# Main.net
KiCad netlist of a schematic drawn in Altium Designer
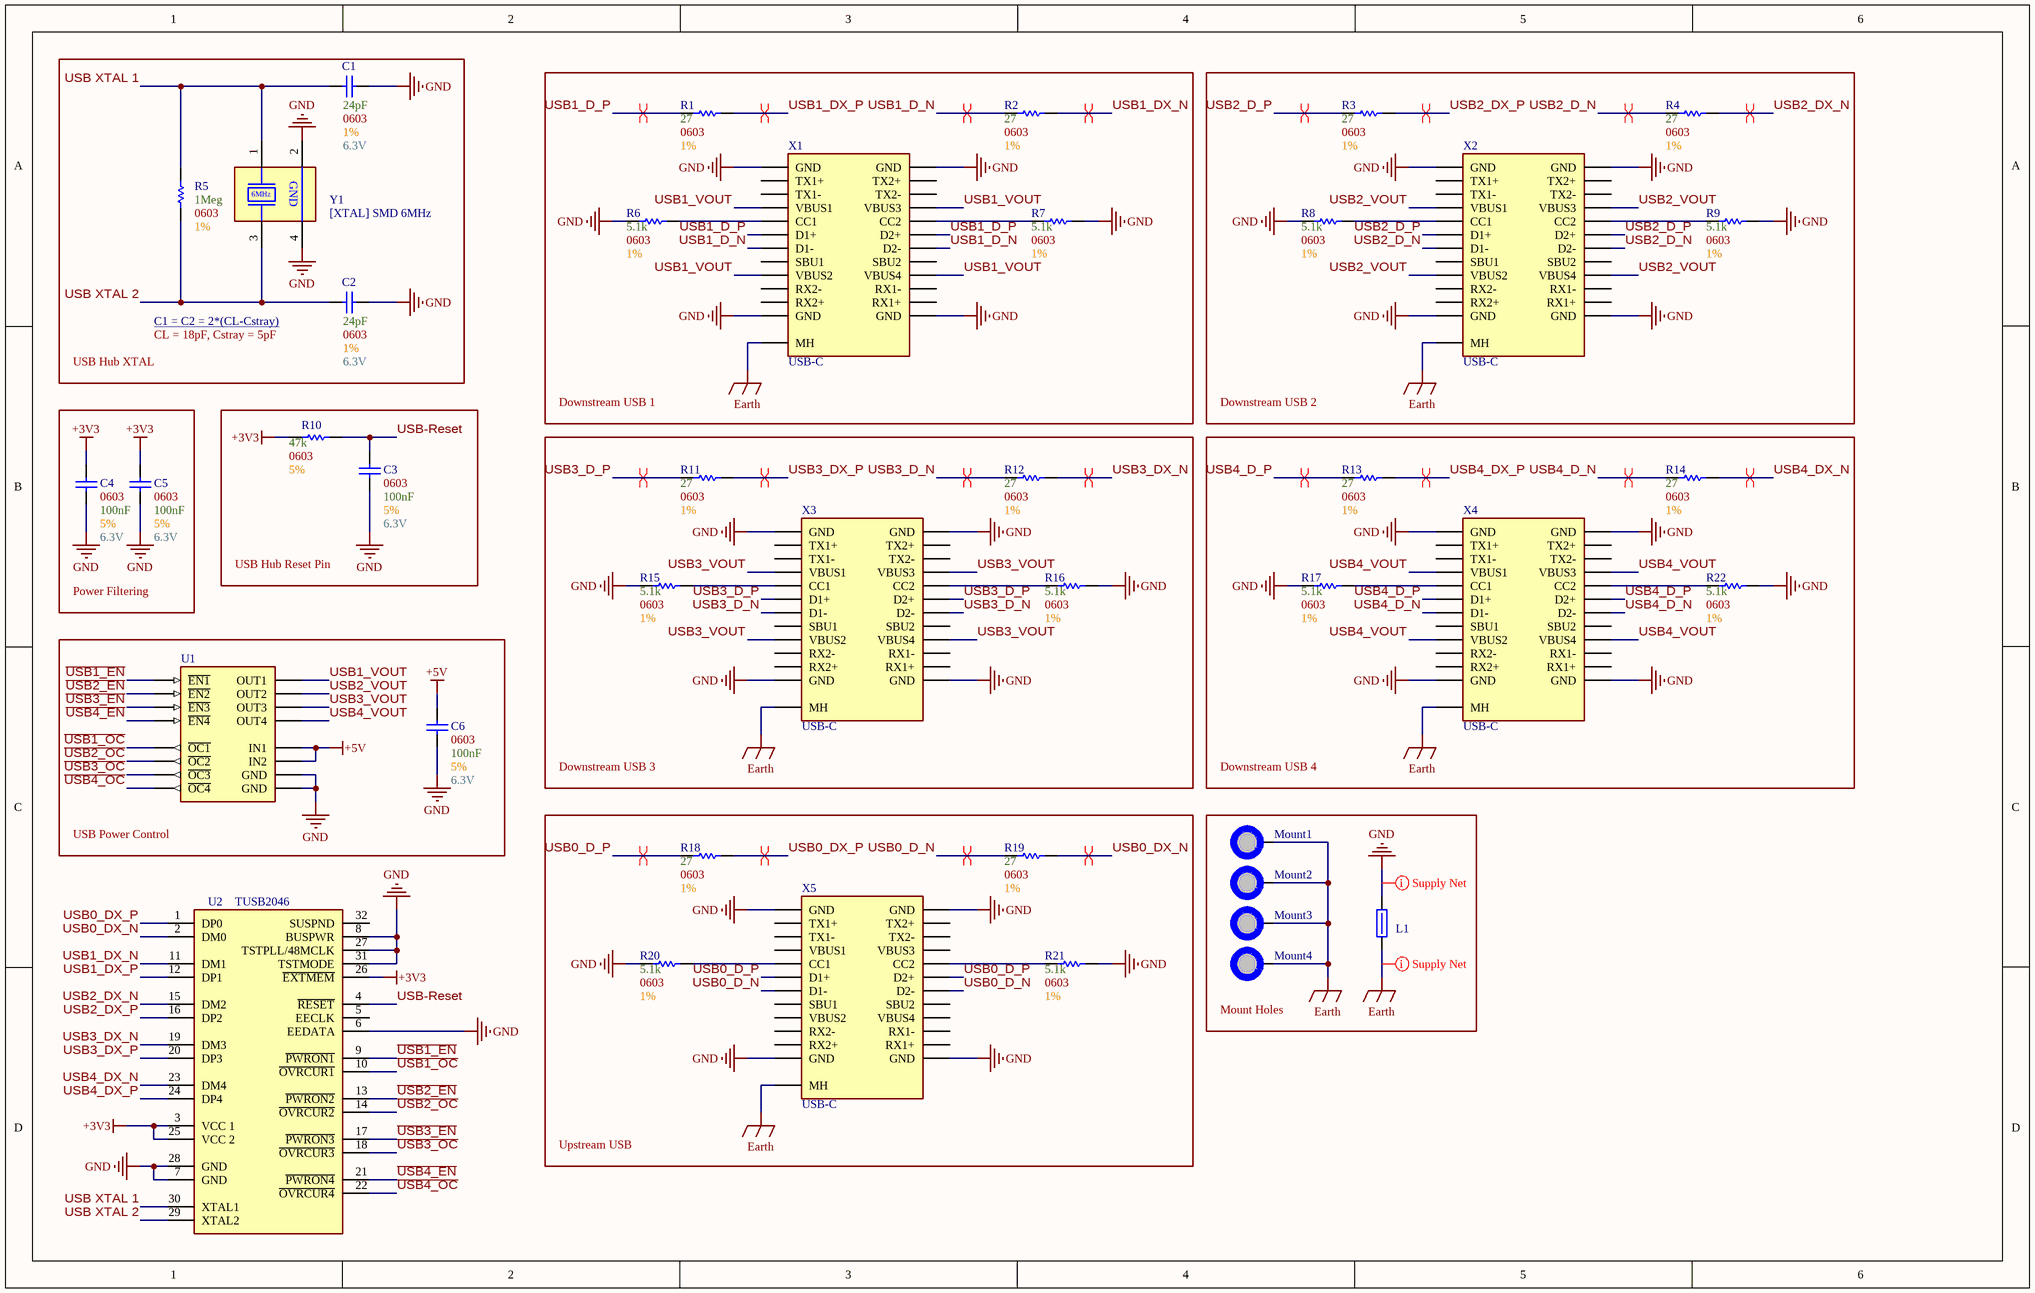
[diagram p0: Main.SchDoc]

(export (version "E")
  (design (tool "Eeschema 10.0.6"))
  (components
    (comp (ref "C1")
      (value "SMD Nonpolarized")
      (footprint "[Cap] SMD 0603")
      (fields
        (field (name "TOLERANCE") "1%")
        (field (name "SIZE PACKAGE") "0603")
        (field (name "CAPACITANCE") "24pF")
        (field (name "VOLTAGE") "6.3V")
      )
      (libsource (lib "RADM Components") (part "[Cap] SMD Nonpolarized"))
    )
    (comp (ref "C2")
      (value "SMD Nonpolarized")
      (footprint "[Cap] SMD 0603")
      (fields
        (field (name "TOLERANCE") "1%")
        (field (name "SIZE PACKAGE") "0603")
        (field (name "CAPACITANCE") "24pF")
        (field (name "VOLTAGE") "6.3V")
      )
      (libsource (lib "RADM Components") (part "[Cap] SMD Nonpolarized"))
    )
    (comp (ref "C3")
      (value "[Cap] SMD Nonpolarized")
      (footprint "[Cap] SMD 0603")
      (fields
        (field (name "SIZE PACKAGE") "0603")
        (field (name "CAPACITANCE") "100nF")
        (field (name "VOLTAGE") "6.3V")
        (field (name "TOLERANCE") "5%")
      )
      (libsource (lib "RADM Components") (part "[Cap] SMD Nonpolarized"))
    )
    (comp (ref "C4")
      (value "[Cap] SMD Nonpolarized")
      (footprint "[Cap] SMD 0603")
      (fields
        (field (name "SIZE PACKAGE") "0603")
        (field (name "CAPACITANCE") "100nF")
        (field (name "VOLTAGE") "6.3V")
        (field (name "TOLERANCE") "5%")
      )
      (libsource (lib "RADM Components") (part "[Cap] SMD Nonpolarized"))
    )
    (comp (ref "C5")
      (value "[Cap] SMD Nonpolarized")
      (footprint "[Cap] SMD 0603")
      (fields
        (field (name "SIZE PACKAGE") "0603")
        (field (name "CAPACITANCE") "100nF")
        (field (name "VOLTAGE") "6.3V")
        (field (name "TOLERANCE") "5%")
      )
      (libsource (lib "RADM Components") (part "[Cap] SMD Nonpolarized"))
    )
    (comp (ref "C6")
      (value "[Cap] SMD Nonpolarized")
      (footprint "[Cap] SMD 0603")
      (fields
        (field (name "SIZE PACKAGE") "0603")
        (field (name "CAPACITANCE") "100nF")
        (field (name "VOLTAGE") "6.3V")
        (field (name "TOLERANCE") "5%")
      )
      (libsource (lib "RADM Components") (part "[Cap] SMD Nonpolarized"))
    )
    (comp (ref "L1")
      (value "652-MH2029-300Y")
      (footprint "[Ferrite] SMD Bead 0805 (1)")
      (libsource (lib "RADM Components") (part "[Ferrite] SMD Ferrite Bead (1)"))
    )
    (comp (ref "Mount1")
      (value "M3 Mount Hole")
      (footprint "[Mount] M3 Mount Hole")
      (description "Place at least 4.5mm from board edge. Plated.")
      (libsource (lib "RADM Connectors") (part "[Mount] M3 Mount Hole"))
    )
    (comp (ref "Mount2")
      (value "M3 Mount Hole")
      (footprint "[Mount] M3 Mount Hole")
      (description "Place at least 4.5mm from board edge. Plated.")
      (libsource (lib "RADM Connectors") (part "[Mount] M3 Mount Hole"))
    )
    (comp (ref "Mount3")
      (value "M3 Mount Hole")
      (footprint "[Mount] M3 Mount Hole")
      (description "Place at least 4.5mm from board edge. Plated.")
      (libsource (lib "RADM Connectors") (part "[Mount] M3 Mount Hole"))
    )
    (comp (ref "Mount4")
      (value "M3 Mount Hole")
      (footprint "[Mount] M3 Mount Hole")
      (description "Place at least 4.5mm from board edge. Plated.")
      (libsource (lib "RADM Connectors") (part "[Mount] M3 Mount Hole"))
    )
    (comp (ref "R1")
      (value "[Res] SMD Resistor")
      (footprint "[Res] SMD 0603")
      (description "Generic")
      (fields
        (field (name "TOLERANCE") "1%")
        (field (name "RESISTANCE") "27")
        (field (name "SIZE PACKAGE") "0603")
      )
      (libsource (lib "RADM Components") (part "[Res] SMD Resistor"))
    )
    (comp (ref "R2")
      (value "[Res] SMD Resistor")
      (footprint "[Res] SMD 0603")
      (description "Generic")
      (fields
        (field (name "TOLERANCE") "1%")
        (field (name "RESISTANCE") "27")
        (field (name "SIZE PACKAGE") "0603")
      )
      (libsource (lib "RADM Components") (part "[Res] SMD Resistor"))
    )
    (comp (ref "R3")
      (value "[Res] SMD Resistor")
      (footprint "[Res] SMD 0603")
      (description "Generic")
      (fields
        (field (name "TOLERANCE") "1%")
        (field (name "RESISTANCE") "27")
        (field (name "SIZE PACKAGE") "0603")
      )
      (libsource (lib "RADM Components") (part "[Res] SMD Resistor"))
    )
    (comp (ref "R4")
      (value "[Res] SMD Resistor")
      (footprint "[Res] SMD 0603")
      (description "Generic")
      (fields
        (field (name "TOLERANCE") "1%")
        (field (name "RESISTANCE") "27")
        (field (name "SIZE PACKAGE") "0603")
      )
      (libsource (lib "RADM Components") (part "[Res] SMD Resistor"))
    )
    (comp (ref "R5")
      (value "[Res] SMD Resistor")
      (footprint "[Res] SMD 0603")
      (description "Generic")
      (fields
        (field (name "TOLERANCE") "1%")
        (field (name "RESISTANCE") "1Meg")
        (field (name "SIZE PACKAGE") "0603")
      )
      (libsource (lib "RADM Components") (part "[Res] SMD Resistor"))
    )
    (comp (ref "R6")
      (value "[Res] SMD Resistor")
      (footprint "[Res] SMD 0603")
      (description "Generic")
      (fields
        (field (name "TOLERANCE") "1%")
        (field (name "RESISTANCE") "5.1k")
        (field (name "SIZE PACKAGE") "0603")
      )
      (libsource (lib "RADM Components") (part "[Res] SMD Resistor"))
    )
    (comp (ref "R7")
      (value "[Res] SMD Resistor")
      (footprint "[Res] SMD 0603")
      (description "Generic")
      (fields
        (field (name "TOLERANCE") "1%")
        (field (name "RESISTANCE") "5.1k")
        (field (name "SIZE PACKAGE") "0603")
      )
      (libsource (lib "RADM Components") (part "[Res] SMD Resistor"))
    )
    (comp (ref "R8")
      (value "[Res] SMD Resistor")
      (footprint "[Res] SMD 0603")
      (description "Generic")
      (fields
        (field (name "TOLERANCE") "1%")
        (field (name "RESISTANCE") "5.1k")
        (field (name "SIZE PACKAGE") "0603")
      )
      (libsource (lib "RADM Components") (part "[Res] SMD Resistor"))
    )
    (comp (ref "R9")
      (value "[Res] SMD Resistor")
      (footprint "[Res] SMD 0603")
      (description "Generic")
      (fields
        (field (name "TOLERANCE") "1%")
        (field (name "RESISTANCE") "5.1k")
        (field (name "SIZE PACKAGE") "0603")
      )
      (libsource (lib "RADM Components") (part "[Res] SMD Resistor"))
    )
    (comp (ref "R10")
      (value "[Res] SMD Resistor")
      (footprint "[Res] SMD 0603")
      (description "Generic")
      (fields
        (field (name "TOLERANCE") "5%")
        (field (name "RESISTANCE") "47k")
        (field (name "SIZE PACKAGE") "0603")
      )
      (libsource (lib "RADM Components") (part "[Res] SMD Resistor"))
    )
    (comp (ref "R11")
      (value "[Res] SMD Resistor")
      (footprint "[Res] SMD 0603")
      (description "Generic")
      (fields
        (field (name "TOLERANCE") "1%")
        (field (name "RESISTANCE") "27")
        (field (name "SIZE PACKAGE") "0603")
      )
      (libsource (lib "RADM Components") (part "[Res] SMD Resistor"))
    )
    (comp (ref "R12")
      (value "[Res] SMD Resistor")
      (footprint "[Res] SMD 0603")
      (description "Generic")
      (fields
        (field (name "TOLERANCE") "1%")
        (field (name "RESISTANCE") "27")
        (field (name "SIZE PACKAGE") "0603")
      )
      (libsource (lib "RADM Components") (part "[Res] SMD Resistor"))
    )
    (comp (ref "R13")
      (value "[Res] SMD Resistor")
      (footprint "[Res] SMD 0603")
      (description "Generic")
      (fields
        (field (name "TOLERANCE") "1%")
        (field (name "RESISTANCE") "27")
        (field (name "SIZE PACKAGE") "0603")
      )
      (libsource (lib "RADM Components") (part "[Res] SMD Resistor"))
    )
    (comp (ref "R14")
      (value "[Res] SMD Resistor")
      (footprint "[Res] SMD 0603")
      (description "Generic")
      (fields
        (field (name "TOLERANCE") "1%")
        (field (name "RESISTANCE") "27")
        (field (name "SIZE PACKAGE") "0603")
      )
      (libsource (lib "RADM Components") (part "[Res] SMD Resistor"))
    )
    (comp (ref "R15")
      (value "[Res] SMD Resistor")
      (footprint "[Res] SMD 0603")
      (description "Generic")
      (fields
        (field (name "TOLERANCE") "1%")
        (field (name "RESISTANCE") "5.1k")
        (field (name "SIZE PACKAGE") "0603")
      )
      (libsource (lib "RADM Components") (part "[Res] SMD Resistor"))
    )
    (comp (ref "R16")
      (value "[Res] SMD Resistor")
      (footprint "[Res] SMD 0603")
      (description "Generic")
      (fields
        (field (name "TOLERANCE") "1%")
        (field (name "RESISTANCE") "5.1k")
        (field (name "SIZE PACKAGE") "0603")
      )
      (libsource (lib "RADM Components") (part "[Res] SMD Resistor"))
    )
    (comp (ref "R17")
      (value "[Res] SMD Resistor")
      (footprint "[Res] SMD 0603")
      (description "Generic")
      (fields
        (field (name "TOLERANCE") "1%")
        (field (name "RESISTANCE") "5.1k")
        (field (name "SIZE PACKAGE") "0603")
      )
      (libsource (lib "RADM Components") (part "[Res] SMD Resistor"))
    )
    (comp (ref "R18")
      (value "[Res] SMD Resistor")
      (footprint "[Res] SMD 0603")
      (description "Generic")
      (fields
        (field (name "TOLERANCE") "1%")
        (field (name "RESISTANCE") "27")
        (field (name "SIZE PACKAGE") "0603")
      )
      (libsource (lib "RADM Components") (part "[Res] SMD Resistor"))
    )
    (comp (ref "R19")
      (value "[Res] SMD Resistor")
      (footprint "[Res] SMD 0603")
      (description "Generic")
      (fields
        (field (name "TOLERANCE") "1%")
        (field (name "RESISTANCE") "27")
        (field (name "SIZE PACKAGE") "0603")
      )
      (libsource (lib "RADM Components") (part "[Res] SMD Resistor"))
    )
    (comp (ref "R20")
      (value "[Res] SMD Resistor")
      (footprint "[Res] SMD 0603")
      (description "Generic")
      (fields
        (field (name "TOLERANCE") "1%")
        (field (name "RESISTANCE") "5.1k")
        (field (name "SIZE PACKAGE") "0603")
      )
      (libsource (lib "RADM Components") (part "[Res] SMD Resistor"))
    )
    (comp (ref "R21")
      (value "[Res] SMD Resistor")
      (footprint "[Res] SMD 0603")
      (description "Generic")
      (fields
        (field (name "TOLERANCE") "1%")
        (field (name "RESISTANCE") "5.1k")
        (field (name "SIZE PACKAGE") "0603")
      )
      (libsource (lib "RADM Components") (part "[Res] SMD Resistor"))
    )
    (comp (ref "R22")
      (value "[Res] SMD Resistor")
      (footprint "[Res] SMD 0603")
      (description "Generic")
      (fields
        (field (name "TOLERANCE") "1%")
        (field (name "RESISTANCE") "5.1k")
        (field (name "SIZE PACKAGE") "0603")
      )
      (libsource (lib "RADM Components") (part "[Res] SMD Resistor"))
    )
    (comp (ref "U1")
      (value "[IC] USB Hub Power Distribution")
      (footprint "[IC] USB Hub Power Distribution")
      (libsource (lib "RADM Components") (part "[IC] USB Hub Power Distribution"))
    )
    (comp (ref "U2")
      (value "TUSB2046")
      (footprint "[IC] USB Hub 4port (2)")
      (description "TUSB2046BVFR")
      (libsource (lib "RADM Components") (part "[IC] USB Hub 4port (2)"))
    )
    (comp (ref "X1")
      (value "USB-C")
      (footprint "[Port] USB-C")
      (libsource (lib "RADM Connectors") (part "[Port] USB Type-C"))
    )
    (comp (ref "X2")
      (value "USB-C")
      (footprint "[Port] USB-C")
      (libsource (lib "RADM Connectors") (part "[Port] USB Type-C"))
    )
    (comp (ref "X3")
      (value "USB-C")
      (footprint "[Port] USB-C")
      (libsource (lib "RADM Connectors") (part "[Port] USB Type-C"))
    )
    (comp (ref "X4")
      (value "USB-C")
      (footprint "[Port] USB-C")
      (libsource (lib "RADM Connectors") (part "[Port] USB Type-C"))
    )
    (comp (ref "X5")
      (value "USB-C")
      (footprint "[Port] USB-C")
      (libsource (lib "RADM Connectors") (part "[Port] USB Type-C"))
    )
    (comp (ref "Y1")
      (value "[XTAL] SMD 6MHz")
      (footprint "[XTAL] SMD 6MHz")
      (description "ECS-060-18-20BM-JEN-TR")
      (libsource (lib "RADM Components") (part "[XTAL] SMD 6MHz"))
    )
  )
  (nets
    (net (code "1") (name "+3V3") (class "Default")
      (node (ref "C4") (pin "2") (pinfunction "2_2") (pintype "passive"))
      (node (ref "C5") (pin "2") (pinfunction "2_2") (pintype "passive"))
      (node (ref "R10") (pin "1") (pinfunction "1_1") (pintype "passive"))
      (node (ref "U2") (pin "25") (pinfunction "VCC_2_25") (pintype "passive"))
      (node (ref "U2") (pin "26") (pinfunction "~{EXTMEM}_26") (pintype "passive"))
      (node (ref "U2") (pin "3") (pinfunction "VCC_1_3") (pintype "passive"))
    )
    (net (code "2") (name "+5V") (class "Default")
      (node (ref "C6") (pin "2") (pinfunction "2_2") (pintype "passive"))
      (node (ref "U1") (pin "2") (pinfunction "IN1_2") (pintype "power_in"))
      (node (ref "U1") (pin "6") (pinfunction "IN2_6") (pintype "power_in"))
    )
    (net (code "3") (name "/USB XTAL 1") (class "Default")
      (node (ref "C1") (pin "1") (pinfunction "1_1") (pintype "passive"))
      (node (ref "R5") (pin "1") (pinfunction "1_1") (pintype "passive"))
      (node (ref "U2") (pin "30") (pinfunction "XTAL1_30") (pintype "passive"))
      (node (ref "Y1") (pin "1") (pinfunction "XTAL1_1") (pintype "power_in"))
    )
    (net (code "4") (name "/USB XTAL 2") (class "Default")
      (node (ref "C2") (pin "1") (pinfunction "1_1") (pintype "passive"))
      (node (ref "R5") (pin "2") (pinfunction "2_2") (pintype "passive"))
      (node (ref "U2") (pin "29") (pinfunction "XTAL2_29") (pintype "passive"))
      (node (ref "Y1") (pin "3") (pinfunction "XTAL2_3") (pintype "power_in"))
    )
    (net (code "5") (name "/USB-Reset") (class "Default")
      (node (ref "C3") (pin "2") (pinfunction "2_2") (pintype "passive"))
      (node (ref "R10") (pin "2") (pinfunction "2_2") (pintype "passive"))
      (node (ref "U2") (pin "4") (pinfunction "~{RESET}_4") (pintype "passive"))
    )
    (net (code "6") (name "/USB0_DX_N") (class "Default")
      (node (ref "R19") (pin "2") (pinfunction "2_2") (pintype "passive"))
      (node (ref "U2") (pin "2") (pinfunction "DM0_2") (pintype "passive"))
    )
    (net (code "7") (name "/USB0_DX_P") (class "Default")
      (node (ref "R18") (pin "2") (pinfunction "2_2") (pintype "passive"))
      (node (ref "U2") (pin "1") (pinfunction "DP0_1") (pintype "passive"))
    )
    (net (code "8") (name "/USB0_D_N") (class "Default")
      (node (ref "R19") (pin "1") (pinfunction "1_1") (pintype "passive"))
      (node (ref "X5") (pin "A7") (pinfunction "D1-_A7") (pintype "passive"))
      (node (ref "X5") (pin "B7") (pinfunction "D2-_B7") (pintype "passive"))
    )
    (net (code "9") (name "/USB0_D_P") (class "Default")
      (node (ref "R18") (pin "1") (pinfunction "1_1") (pintype "passive"))
      (node (ref "X5") (pin "A6") (pinfunction "D1+_A6") (pintype "passive"))
      (node (ref "X5") (pin "B6") (pinfunction "D2+_B6") (pintype "passive"))
    )
    (net (code "10") (name "/USB1_DX_N") (class "Default")
      (node (ref "R2") (pin "2") (pinfunction "2_2") (pintype "passive"))
      (node (ref "U2") (pin "11") (pinfunction "DM1_11") (pintype "passive"))
    )
    (net (code "11") (name "/USB1_DX_P") (class "Default")
      (node (ref "R1") (pin "2") (pinfunction "2_2") (pintype "passive"))
      (node (ref "U2") (pin "12") (pinfunction "DP1_12") (pintype "passive"))
    )
    (net (code "12") (name "/USB1_D_N") (class "Default")
      (node (ref "R2") (pin "1") (pinfunction "1_1") (pintype "passive"))
      (node (ref "X1") (pin "A7") (pinfunction "D1-_A7") (pintype "passive"))
      (node (ref "X1") (pin "B7") (pinfunction "D2-_B7") (pintype "passive"))
    )
    (net (code "13") (name "/USB1_D_P") (class "Default")
      (node (ref "R1") (pin "1") (pinfunction "1_1") (pintype "passive"))
      (node (ref "X1") (pin "A6") (pinfunction "D1+_A6") (pintype "passive"))
      (node (ref "X1") (pin "B6") (pinfunction "D2+_B6") (pintype "passive"))
    )
    (net (code "14") (name "/USB1_EN") (class "Default")
      (node (ref "U1") (pin "3") (pinfunction "~{EN1}_3") (pintype "input"))
      (node (ref "U2") (pin "9") (pinfunction "~{PWRON1}_9") (pintype "passive"))
    )
    (net (code "15") (name "/USB1_OC") (class "Default")
      (node (ref "U1") (pin "16") (pinfunction "~{OC1}_16") (pintype "output"))
      (node (ref "U2") (pin "10") (pinfunction "~{OVRCUR1}_10") (pintype "passive"))
    )
    (net (code "16") (name "/USB1_VOUT") (class "Default")
      (node (ref "U1") (pin "15") (pinfunction "OUT1_15") (pintype "power_in"))
      (node (ref "X1") (pin "A4") (pinfunction "VBUS1_A4") (pintype "passive"))
      (node (ref "X1") (pin "A9") (pinfunction "VBUS2_A9") (pintype "passive"))
      (node (ref "X1") (pin "B4") (pinfunction "VBUS3_B4") (pintype "passive"))
      (node (ref "X1") (pin "B9") (pinfunction "VBUS4_B9") (pintype "passive"))
    )
    (net (code "17") (name "/USB2_DX_N") (class "Default")
      (node (ref "R4") (pin "2") (pinfunction "2_2") (pintype "passive"))
      (node (ref "U2") (pin "15") (pinfunction "DM2_15") (pintype "passive"))
    )
    (net (code "18") (name "/USB2_DX_P") (class "Default")
      (node (ref "R3") (pin "2") (pinfunction "2_2") (pintype "passive"))
      (node (ref "U2") (pin "16") (pinfunction "DP2_16") (pintype "passive"))
    )
    (net (code "19") (name "/USB2_D_N") (class "Default")
      (node (ref "R4") (pin "1") (pinfunction "1_1") (pintype "passive"))
      (node (ref "X2") (pin "A7") (pinfunction "D1-_A7") (pintype "passive"))
      (node (ref "X2") (pin "B7") (pinfunction "D2-_B7") (pintype "passive"))
    )
    (net (code "20") (name "/USB2_D_P") (class "Default")
      (node (ref "R3") (pin "1") (pinfunction "1_1") (pintype "passive"))
      (node (ref "X2") (pin "A6") (pinfunction "D1+_A6") (pintype "passive"))
      (node (ref "X2") (pin "B6") (pinfunction "D2+_B6") (pintype "passive"))
    )
    (net (code "21") (name "/USB2_EN") (class "Default")
      (node (ref "U1") (pin "4") (pinfunction "~{EN2}_4") (pintype "input"))
      (node (ref "U2") (pin "13") (pinfunction "~{PWRON2}_13") (pintype "passive"))
    )
    (net (code "22") (name "/USB2_OC") (class "Default")
      (node (ref "U1") (pin "13") (pinfunction "~{OC2}_13") (pintype "output"))
      (node (ref "U2") (pin "14") (pinfunction "~{OVRCUR2}_14") (pintype "passive"))
    )
    (net (code "23") (name "/USB2_VOUT") (class "Default")
      (node (ref "U1") (pin "14") (pinfunction "OUT2_14") (pintype "power_in"))
      (node (ref "X2") (pin "A4") (pinfunction "VBUS1_A4") (pintype "passive"))
      (node (ref "X2") (pin "A9") (pinfunction "VBUS2_A9") (pintype "passive"))
      (node (ref "X2") (pin "B4") (pinfunction "VBUS3_B4") (pintype "passive"))
      (node (ref "X2") (pin "B9") (pinfunction "VBUS4_B9") (pintype "passive"))
    )
    (net (code "24") (name "/USB3_DX_N") (class "Default")
      (node (ref "R12") (pin "2") (pinfunction "2_2") (pintype "passive"))
      (node (ref "U2") (pin "19") (pinfunction "DM3_19") (pintype "passive"))
    )
    (net (code "25") (name "/USB3_DX_P") (class "Default")
      (node (ref "R11") (pin "2") (pinfunction "2_2") (pintype "passive"))
      (node (ref "U2") (pin "20") (pinfunction "DP3_20") (pintype "passive"))
    )
    (net (code "26") (name "/USB3_D_N") (class "Default")
      (node (ref "R12") (pin "1") (pinfunction "1_1") (pintype "passive"))
      (node (ref "X3") (pin "A7") (pinfunction "D1-_A7") (pintype "passive"))
      (node (ref "X3") (pin "B7") (pinfunction "D2-_B7") (pintype "passive"))
    )
    (net (code "27") (name "/USB3_D_P") (class "Default")
      (node (ref "R11") (pin "1") (pinfunction "1_1") (pintype "passive"))
      (node (ref "X3") (pin "A6") (pinfunction "D1+_A6") (pintype "passive"))
      (node (ref "X3") (pin "B6") (pinfunction "D2+_B6") (pintype "passive"))
    )
    (net (code "28") (name "/USB3_EN") (class "Default")
      (node (ref "U1") (pin "7") (pinfunction "~{EN3}_7") (pintype "input"))
      (node (ref "U2") (pin "17") (pinfunction "~{PWRON3}_17") (pintype "passive"))
    )
    (net (code "29") (name "/USB3_OC") (class "Default")
      (node (ref "U1") (pin "12") (pinfunction "~{OC3}_12") (pintype "output"))
      (node (ref "U2") (pin "18") (pinfunction "~{OVRCUR3}_18") (pintype "passive"))
    )
    (net (code "30") (name "/USB3_VOUT") (class "Default")
      (node (ref "U1") (pin "11") (pinfunction "OUT3_11") (pintype "power_in"))
      (node (ref "X3") (pin "A4") (pinfunction "VBUS1_A4") (pintype "passive"))
      (node (ref "X3") (pin "A9") (pinfunction "VBUS2_A9") (pintype "passive"))
      (node (ref "X3") (pin "B4") (pinfunction "VBUS3_B4") (pintype "passive"))
      (node (ref "X3") (pin "B9") (pinfunction "VBUS4_B9") (pintype "passive"))
    )
    (net (code "31") (name "/USB4_DX_N") (class "Default")
      (node (ref "R14") (pin "2") (pinfunction "2_2") (pintype "passive"))
      (node (ref "U2") (pin "23") (pinfunction "DM4_23") (pintype "passive"))
    )
    (net (code "32") (name "/USB4_DX_P") (class "Default")
      (node (ref "R13") (pin "2") (pinfunction "2_2") (pintype "passive"))
      (node (ref "U2") (pin "24") (pinfunction "DP4_24") (pintype "passive"))
    )
    (net (code "33") (name "/USB4_D_N") (class "Default")
      (node (ref "R14") (pin "1") (pinfunction "1_1") (pintype "passive"))
      (node (ref "X4") (pin "A7") (pinfunction "D1-_A7") (pintype "passive"))
      (node (ref "X4") (pin "B7") (pinfunction "D2-_B7") (pintype "passive"))
    )
    (net (code "34") (name "/USB4_D_P") (class "Default")
      (node (ref "R13") (pin "1") (pinfunction "1_1") (pintype "passive"))
      (node (ref "X4") (pin "A6") (pinfunction "D1+_A6") (pintype "passive"))
      (node (ref "X4") (pin "B6") (pinfunction "D2+_B6") (pintype "passive"))
    )
    (net (code "35") (name "/USB4_EN") (class "Default")
      (node (ref "U1") (pin "8") (pinfunction "~{EN4}_8") (pintype "input"))
      (node (ref "U2") (pin "21") (pinfunction "~{PWRON4}_21") (pintype "passive"))
    )
    (net (code "36") (name "/USB4_OC") (class "Default")
      (node (ref "U1") (pin "9") (pinfunction "~{OC4}_9") (pintype "output"))
      (node (ref "U2") (pin "22") (pinfunction "~{OVRCUR4}_22") (pintype "passive"))
    )
    (net (code "37") (name "/USB4_VOUT") (class "Default")
      (node (ref "U1") (pin "10") (pinfunction "OUT4_10") (pintype "power_in"))
      (node (ref "X4") (pin "A4") (pinfunction "VBUS1_A4") (pintype "passive"))
      (node (ref "X4") (pin "A9") (pinfunction "VBUS2_A9") (pintype "passive"))
      (node (ref "X4") (pin "B4") (pinfunction "VBUS3_B4") (pintype "passive"))
      (node (ref "X4") (pin "B9") (pinfunction "VBUS4_B9") (pintype "passive"))
    )
    (net (code "38") (name "Earth") (class "Default")
      (node (ref "L1") (pin "1") (pinfunction "1_1") (pintype "passive"))
      (node (ref "Mount1") (pin "1") (pintype "power_in"))
      (node (ref "Mount2") (pin "1") (pintype "power_in"))
      (node (ref "Mount3") (pin "1") (pintype "power_in"))
      (node (ref "Mount4") (pin "1") (pintype "power_in"))
      (node (ref "X1") (pin "MH") (pinfunction "MH_MH") (pintype "passive"))
      (node (ref "X2") (pin "MH") (pinfunction "MH_MH") (pintype "passive"))
      (node (ref "X3") (pin "MH") (pinfunction "MH_MH") (pintype "passive"))
      (node (ref "X4") (pin "MH") (pinfunction "MH_MH") (pintype "passive"))
      (node (ref "X5") (pin "MH") (pinfunction "MH_MH") (pintype "passive"))
    )
    (net (code "39") (name "GND") (class "Default")
      (node (ref "C1") (pin "2") (pinfunction "2_2") (pintype "passive"))
      (node (ref "C2") (pin "2") (pinfunction "2_2") (pintype "passive"))
      (node (ref "C3") (pin "1") (pinfunction "1_1") (pintype "passive"))
      (node (ref "C4") (pin "1") (pinfunction "1_1") (pintype "passive"))
      (node (ref "C5") (pin "1") (pinfunction "1_1") (pintype "passive"))
      (node (ref "C6") (pin "1") (pinfunction "1_1") (pintype "passive"))
      (node (ref "L1") (pin "2") (pinfunction "2_2") (pintype "passive"))
      (node (ref "R15") (pin "1") (pinfunction "1_1") (pintype "passive"))
      (node (ref "R16") (pin "2") (pinfunction "2_2") (pintype "passive"))
      (node (ref "R17") (pin "1") (pinfunction "1_1") (pintype "passive"))
      (node (ref "R20") (pin "1") (pinfunction "1_1") (pintype "passive"))
      (node (ref "R21") (pin "2") (pinfunction "2_2") (pintype "passive"))
      (node (ref "R22") (pin "2") (pinfunction "2_2") (pintype "passive"))
      (node (ref "R6") (pin "1") (pinfunction "1_1") (pintype "passive"))
      (node (ref "R7") (pin "2") (pinfunction "2_2") (pintype "passive"))
      (node (ref "R8") (pin "1") (pinfunction "1_1") (pintype "passive"))
      (node (ref "R9") (pin "2") (pinfunction "2_2") (pintype "passive"))
      (node (ref "U1") (pin "1") (pinfunction "GND_1") (pintype "power_in"))
      (node (ref "U1") (pin "5") (pinfunction "GND_5") (pintype "power_in"))
      (node (ref "U2") (pin "27") (pinfunction "TSTPLL/48MCLK_27") (pintype "passive"))
      (node (ref "U2") (pin "28") (pinfunction "GND_28") (pintype "passive"))
      (node (ref "U2") (pin "31") (pinfunction "TSTMODE_31") (pintype "passive"))
      (node (ref "U2") (pin "6") (pinfunction "EEDATA_6") (pintype "passive"))
      (node (ref "U2") (pin "7") (pinfunction "GND_7") (pintype "passive"))
      (node (ref "U2") (pin "8") (pinfunction "BUSPWR_8") (pintype "passive"))
      (node (ref "X1") (pin "A1") (pinfunction "GND_A1") (pintype "passive"))
      (node (ref "X1") (pin "A12") (pinfunction "GND_A12") (pintype "passive"))
      (node (ref "X1") (pin "B1") (pinfunction "GND_B1") (pintype "passive"))
      (node (ref "X1") (pin "B12") (pinfunction "GND_B12") (pintype "passive"))
      (node (ref "X2") (pin "A1") (pinfunction "GND_A1") (pintype "passive"))
      (node (ref "X2") (pin "A12") (pinfunction "GND_A12") (pintype "passive"))
      (node (ref "X2") (pin "B1") (pinfunction "GND_B1") (pintype "passive"))
      (node (ref "X2") (pin "B12") (pinfunction "GND_B12") (pintype "passive"))
      (node (ref "X3") (pin "A1") (pinfunction "GND_A1") (pintype "passive"))
      (node (ref "X3") (pin "A12") (pinfunction "GND_A12") (pintype "passive"))
      (node (ref "X3") (pin "B1") (pinfunction "GND_B1") (pintype "passive"))
      (node (ref "X3") (pin "B12") (pinfunction "GND_B12") (pintype "passive"))
      (node (ref "X4") (pin "A1") (pinfunction "GND_A1") (pintype "passive"))
      (node (ref "X4") (pin "A12") (pinfunction "GND_A12") (pintype "passive"))
      (node (ref "X4") (pin "B1") (pinfunction "GND_B1") (pintype "passive"))
      (node (ref "X4") (pin "B12") (pinfunction "GND_B12") (pintype "passive"))
      (node (ref "X5") (pin "A1") (pinfunction "GND_A1") (pintype "passive"))
      (node (ref "X5") (pin "A12") (pinfunction "GND_A12") (pintype "passive"))
      (node (ref "X5") (pin "B1") (pinfunction "GND_B1") (pintype "passive"))
      (node (ref "X5") (pin "B12") (pinfunction "GND_B12") (pintype "passive"))
      (node (ref "Y1") (pin "2") (pinfunction "GND_2") (pintype "power_in"))
      (node (ref "Y1") (pin "4") (pinfunction "GND_4") (pintype "power_in"))
    )
    (net (code "40") (name "Net-(X1-CC1)") (class "Default")
      (node (ref "R6") (pin "2") (pinfunction "2_2") (pintype "passive"))
      (node (ref "X1") (pin "A5") (pinfunction "CC1_A5") (pintype "passive"))
    )
    (net (code "41") (name "Net-(X1-CC2)") (class "Default")
      (node (ref "R7") (pin "1") (pinfunction "1_1") (pintype "passive"))
      (node (ref "X1") (pin "B5") (pinfunction "CC2_B5") (pintype "passive"))
    )
    (net (code "42") (name "Net-(X2-CC1)") (class "Default")
      (node (ref "R8") (pin "2") (pinfunction "2_2") (pintype "passive"))
      (node (ref "X2") (pin "A5") (pinfunction "CC1_A5") (pintype "passive"))
    )
    (net (code "43") (name "Net-(X2-CC2)") (class "Default")
      (node (ref "R9") (pin "1") (pinfunction "1_1") (pintype "passive"))
      (node (ref "X2") (pin "B5") (pinfunction "CC2_B5") (pintype "passive"))
    )
    (net (code "44") (name "Net-(X3-CC1)") (class "Default")
      (node (ref "R15") (pin "2") (pinfunction "2_2") (pintype "passive"))
      (node (ref "X3") (pin "A5") (pinfunction "CC1_A5") (pintype "passive"))
    )
    (net (code "45") (name "Net-(X3-CC2)") (class "Default")
      (node (ref "R16") (pin "1") (pinfunction "1_1") (pintype "passive"))
      (node (ref "X3") (pin "B5") (pinfunction "CC2_B5") (pintype "passive"))
    )
    (net (code "46") (name "Net-(X4-CC1)") (class "Default")
      (node (ref "R17") (pin "2") (pinfunction "2_2") (pintype "passive"))
      (node (ref "X4") (pin "A5") (pinfunction "CC1_A5") (pintype "passive"))
    )
    (net (code "47") (name "Net-(X4-CC2)") (class "Default")
      (node (ref "R22") (pin "1") (pinfunction "1_1") (pintype "passive"))
      (node (ref "X4") (pin "B5") (pinfunction "CC2_B5") (pintype "passive"))
    )
    (net (code "48") (name "Net-(X5-CC1)") (class "Default")
      (node (ref "R20") (pin "2") (pinfunction "2_2") (pintype "passive"))
      (node (ref "X5") (pin "A5") (pinfunction "CC1_A5") (pintype "passive"))
    )
    (net (code "49") (name "Net-(X5-CC2)") (class "Default")
      (node (ref "R21") (pin "1") (pinfunction "1_1") (pintype "passive"))
      (node (ref "X5") (pin "B5") (pinfunction "CC2_B5") (pintype "passive"))
    )
    (net (code "50") (name "unconnected-(U2-EECLK-Pad5)") (class "Default")
      (node (ref "U2") (pin "5") (pinfunction "EECLK_5") (pintype "passive"))
    )
    (net (code "51") (name "unconnected-(U2-SUSPND-Pad32)") (class "Default")
      (node (ref "U2") (pin "32") (pinfunction "SUSPND_32") (pintype "passive"))
    )
    (net (code "52") (name "unconnected-(X1-RX1+-PadB11)") (class "Default")
      (node (ref "X1") (pin "B11") (pinfunction "RX1+_B11") (pintype "passive"))
    )
    (net (code "53") (name "unconnected-(X1-RX1--PadB10)") (class "Default")
      (node (ref "X1") (pin "B10") (pinfunction "RX1-_B10") (pintype "passive"))
    )
    (net (code "54") (name "unconnected-(X1-RX2+-PadA11)") (class "Default")
      (node (ref "X1") (pin "A11") (pinfunction "RX2+_A11") (pintype "passive"))
    )
    (net (code "55") (name "unconnected-(X1-RX2--PadA10)") (class "Default")
      (node (ref "X1") (pin "A10") (pinfunction "RX2-_A10") (pintype "passive"))
    )
    (net (code "56") (name "unconnected-(X1-SBU1-PadA8)") (class "Default")
      (node (ref "X1") (pin "A8") (pinfunction "SBU1_A8") (pintype "passive"))
    )
    (net (code "57") (name "unconnected-(X1-SBU2-PadB8)") (class "Default")
      (node (ref "X1") (pin "B8") (pinfunction "SBU2_B8") (pintype "passive"))
    )
    (net (code "58") (name "unconnected-(X1-TX1+-PadA2)") (class "Default")
      (node (ref "X1") (pin "A2") (pinfunction "TX1+_A2") (pintype "passive"))
    )
    (net (code "59") (name "unconnected-(X1-TX1--PadA3)") (class "Default")
      (node (ref "X1") (pin "A3") (pinfunction "TX1-_A3") (pintype "passive"))
    )
    (net (code "60") (name "unconnected-(X1-TX2+-PadB2)") (class "Default")
      (node (ref "X1") (pin "B2") (pinfunction "TX2+_B2") (pintype "passive"))
    )
    (net (code "61") (name "unconnected-(X1-TX2--PadB3)") (class "Default")
      (node (ref "X1") (pin "B3") (pinfunction "TX2-_B3") (pintype "passive"))
    )
    (net (code "62") (name "unconnected-(X2-RX1+-PadB11)") (class "Default")
      (node (ref "X2") (pin "B11") (pinfunction "RX1+_B11") (pintype "passive"))
    )
    (net (code "63") (name "unconnected-(X2-RX1--PadB10)") (class "Default")
      (node (ref "X2") (pin "B10") (pinfunction "RX1-_B10") (pintype "passive"))
    )
    (net (code "64") (name "unconnected-(X2-RX2+-PadA11)") (class "Default")
      (node (ref "X2") (pin "A11") (pinfunction "RX2+_A11") (pintype "passive"))
    )
    (net (code "65") (name "unconnected-(X2-RX2--PadA10)") (class "Default")
      (node (ref "X2") (pin "A10") (pinfunction "RX2-_A10") (pintype "passive"))
    )
    (net (code "66") (name "unconnected-(X2-SBU1-PadA8)") (class "Default")
      (node (ref "X2") (pin "A8") (pinfunction "SBU1_A8") (pintype "passive"))
    )
    (net (code "67") (name "unconnected-(X2-SBU2-PadB8)") (class "Default")
      (node (ref "X2") (pin "B8") (pinfunction "SBU2_B8") (pintype "passive"))
    )
    (net (code "68") (name "unconnected-(X2-TX1+-PadA2)") (class "Default")
      (node (ref "X2") (pin "A2") (pinfunction "TX1+_A2") (pintype "passive"))
    )
    (net (code "69") (name "unconnected-(X2-TX1--PadA3)") (class "Default")
      (node (ref "X2") (pin "A3") (pinfunction "TX1-_A3") (pintype "passive"))
    )
    (net (code "70") (name "unconnected-(X2-TX2+-PadB2)") (class "Default")
      (node (ref "X2") (pin "B2") (pinfunction "TX2+_B2") (pintype "passive"))
    )
    (net (code "71") (name "unconnected-(X2-TX2--PadB3)") (class "Default")
      (node (ref "X2") (pin "B3") (pinfunction "TX2-_B3") (pintype "passive"))
    )
    (net (code "72") (name "unconnected-(X3-RX1+-PadB11)") (class "Default")
      (node (ref "X3") (pin "B11") (pinfunction "RX1+_B11") (pintype "passive"))
    )
    (net (code "73") (name "unconnected-(X3-RX1--PadB10)") (class "Default")
      (node (ref "X3") (pin "B10") (pinfunction "RX1-_B10") (pintype "passive"))
    )
    (net (code "74") (name "unconnected-(X3-RX2+-PadA11)") (class "Default")
      (node (ref "X3") (pin "A11") (pinfunction "RX2+_A11") (pintype "passive"))
    )
    (net (code "75") (name "unconnected-(X3-RX2--PadA10)") (class "Default")
      (node (ref "X3") (pin "A10") (pinfunction "RX2-_A10") (pintype "passive"))
    )
    (net (code "76") (name "unconnected-(X3-SBU1-PadA8)") (class "Default")
      (node (ref "X3") (pin "A8") (pinfunction "SBU1_A8") (pintype "passive"))
    )
    (net (code "77") (name "unconnected-(X3-SBU2-PadB8)") (class "Default")
      (node (ref "X3") (pin "B8") (pinfunction "SBU2_B8") (pintype "passive"))
    )
    (net (code "78") (name "unconnected-(X3-TX1+-PadA2)") (class "Default")
      (node (ref "X3") (pin "A2") (pinfunction "TX1+_A2") (pintype "passive"))
    )
    (net (code "79") (name "unconnected-(X3-TX1--PadA3)") (class "Default")
      (node (ref "X3") (pin "A3") (pinfunction "TX1-_A3") (pintype "passive"))
    )
    (net (code "80") (name "unconnected-(X3-TX2+-PadB2)") (class "Default")
      (node (ref "X3") (pin "B2") (pinfunction "TX2+_B2") (pintype "passive"))
    )
    (net (code "81") (name "unconnected-(X3-TX2--PadB3)") (class "Default")
      (node (ref "X3") (pin "B3") (pinfunction "TX2-_B3") (pintype "passive"))
    )
    (net (code "82") (name "unconnected-(X4-RX1+-PadB11)") (class "Default")
      (node (ref "X4") (pin "B11") (pinfunction "RX1+_B11") (pintype "passive"))
    )
    (net (code "83") (name "unconnected-(X4-RX1--PadB10)") (class "Default")
      (node (ref "X4") (pin "B10") (pinfunction "RX1-_B10") (pintype "passive"))
    )
    (net (code "84") (name "unconnected-(X4-RX2+-PadA11)") (class "Default")
      (node (ref "X4") (pin "A11") (pinfunction "RX2+_A11") (pintype "passive"))
    )
    (net (code "85") (name "unconnected-(X4-RX2--PadA10)") (class "Default")
      (node (ref "X4") (pin "A10") (pinfunction "RX2-_A10") (pintype "passive"))
    )
    (net (code "86") (name "unconnected-(X4-SBU1-PadA8)") (class "Default")
      (node (ref "X4") (pin "A8") (pinfunction "SBU1_A8") (pintype "passive"))
    )
    (net (code "87") (name "unconnected-(X4-SBU2-PadB8)") (class "Default")
      (node (ref "X4") (pin "B8") (pinfunction "SBU2_B8") (pintype "passive"))
    )
    (net (code "88") (name "unconnected-(X4-TX1+-PadA2)") (class "Default")
      (node (ref "X4") (pin "A2") (pinfunction "TX1+_A2") (pintype "passive"))
    )
    (net (code "89") (name "unconnected-(X4-TX1--PadA3)") (class "Default")
      (node (ref "X4") (pin "A3") (pinfunction "TX1-_A3") (pintype "passive"))
    )
    (net (code "90") (name "unconnected-(X4-TX2+-PadB2)") (class "Default")
      (node (ref "X4") (pin "B2") (pinfunction "TX2+_B2") (pintype "passive"))
    )
    (net (code "91") (name "unconnected-(X4-TX2--PadB3)") (class "Default")
      (node (ref "X4") (pin "B3") (pinfunction "TX2-_B3") (pintype "passive"))
    )
    (net (code "92") (name "unconnected-(X5-RX1+-PadB11)") (class "Default")
      (node (ref "X5") (pin "B11") (pinfunction "RX1+_B11") (pintype "passive"))
    )
    (net (code "93") (name "unconnected-(X5-RX1--PadB10)") (class "Default")
      (node (ref "X5") (pin "B10") (pinfunction "RX1-_B10") (pintype "passive"))
    )
    (net (code "94") (name "unconnected-(X5-RX2+-PadA11)") (class "Default")
      (node (ref "X5") (pin "A11") (pinfunction "RX2+_A11") (pintype "passive"))
    )
    (net (code "95") (name "unconnected-(X5-RX2--PadA10)") (class "Default")
      (node (ref "X5") (pin "A10") (pinfunction "RX2-_A10") (pintype "passive"))
    )
    (net (code "96") (name "unconnected-(X5-SBU1-PadA8)") (class "Default")
      (node (ref "X5") (pin "A8") (pinfunction "SBU1_A8") (pintype "passive"))
    )
    (net (code "97") (name "unconnected-(X5-SBU2-PadB8)") (class "Default")
      (node (ref "X5") (pin "B8") (pinfunction "SBU2_B8") (pintype "passive"))
    )
    (net (code "98") (name "unconnected-(X5-TX1+-PadA2)") (class "Default")
      (node (ref "X5") (pin "A2") (pinfunction "TX1+_A2") (pintype "passive"))
    )
    (net (code "99") (name "unconnected-(X5-TX1--PadA3)") (class "Default")
      (node (ref "X5") (pin "A3") (pinfunction "TX1-_A3") (pintype "passive"))
    )
    (net (code "100") (name "unconnected-(X5-TX2+-PadB2)") (class "Default")
      (node (ref "X5") (pin "B2") (pinfunction "TX2+_B2") (pintype "passive"))
    )
    (net (code "101") (name "unconnected-(X5-TX2--PadB3)") (class "Default")
      (node (ref "X5") (pin "B3") (pinfunction "TX2-_B3") (pintype "passive"))
    )
    (net (code "102") (name "unconnected-(X5-VBUS1-PadA4)") (class "Default")
      (node (ref "X5") (pin "A4") (pinfunction "VBUS1_A4") (pintype "passive"))
    )
    (net (code "103") (name "unconnected-(X5-VBUS2-PadA9)") (class "Default")
      (node (ref "X5") (pin "A9") (pinfunction "VBUS2_A9") (pintype "passive"))
    )
    (net (code "104") (name "unconnected-(X5-VBUS3-PadB4)") (class "Default")
      (node (ref "X5") (pin "B4") (pinfunction "VBUS3_B4") (pintype "passive"))
    )
    (net (code "105") (name "unconnected-(X5-VBUS4-PadB9)") (class "Default")
      (node (ref "X5") (pin "B9") (pinfunction "VBUS4_B9") (pintype "passive"))
    )
  )
)
